# Light_Sensor_Card.net
KiCad netlist of a schematic drawn in EAGLE
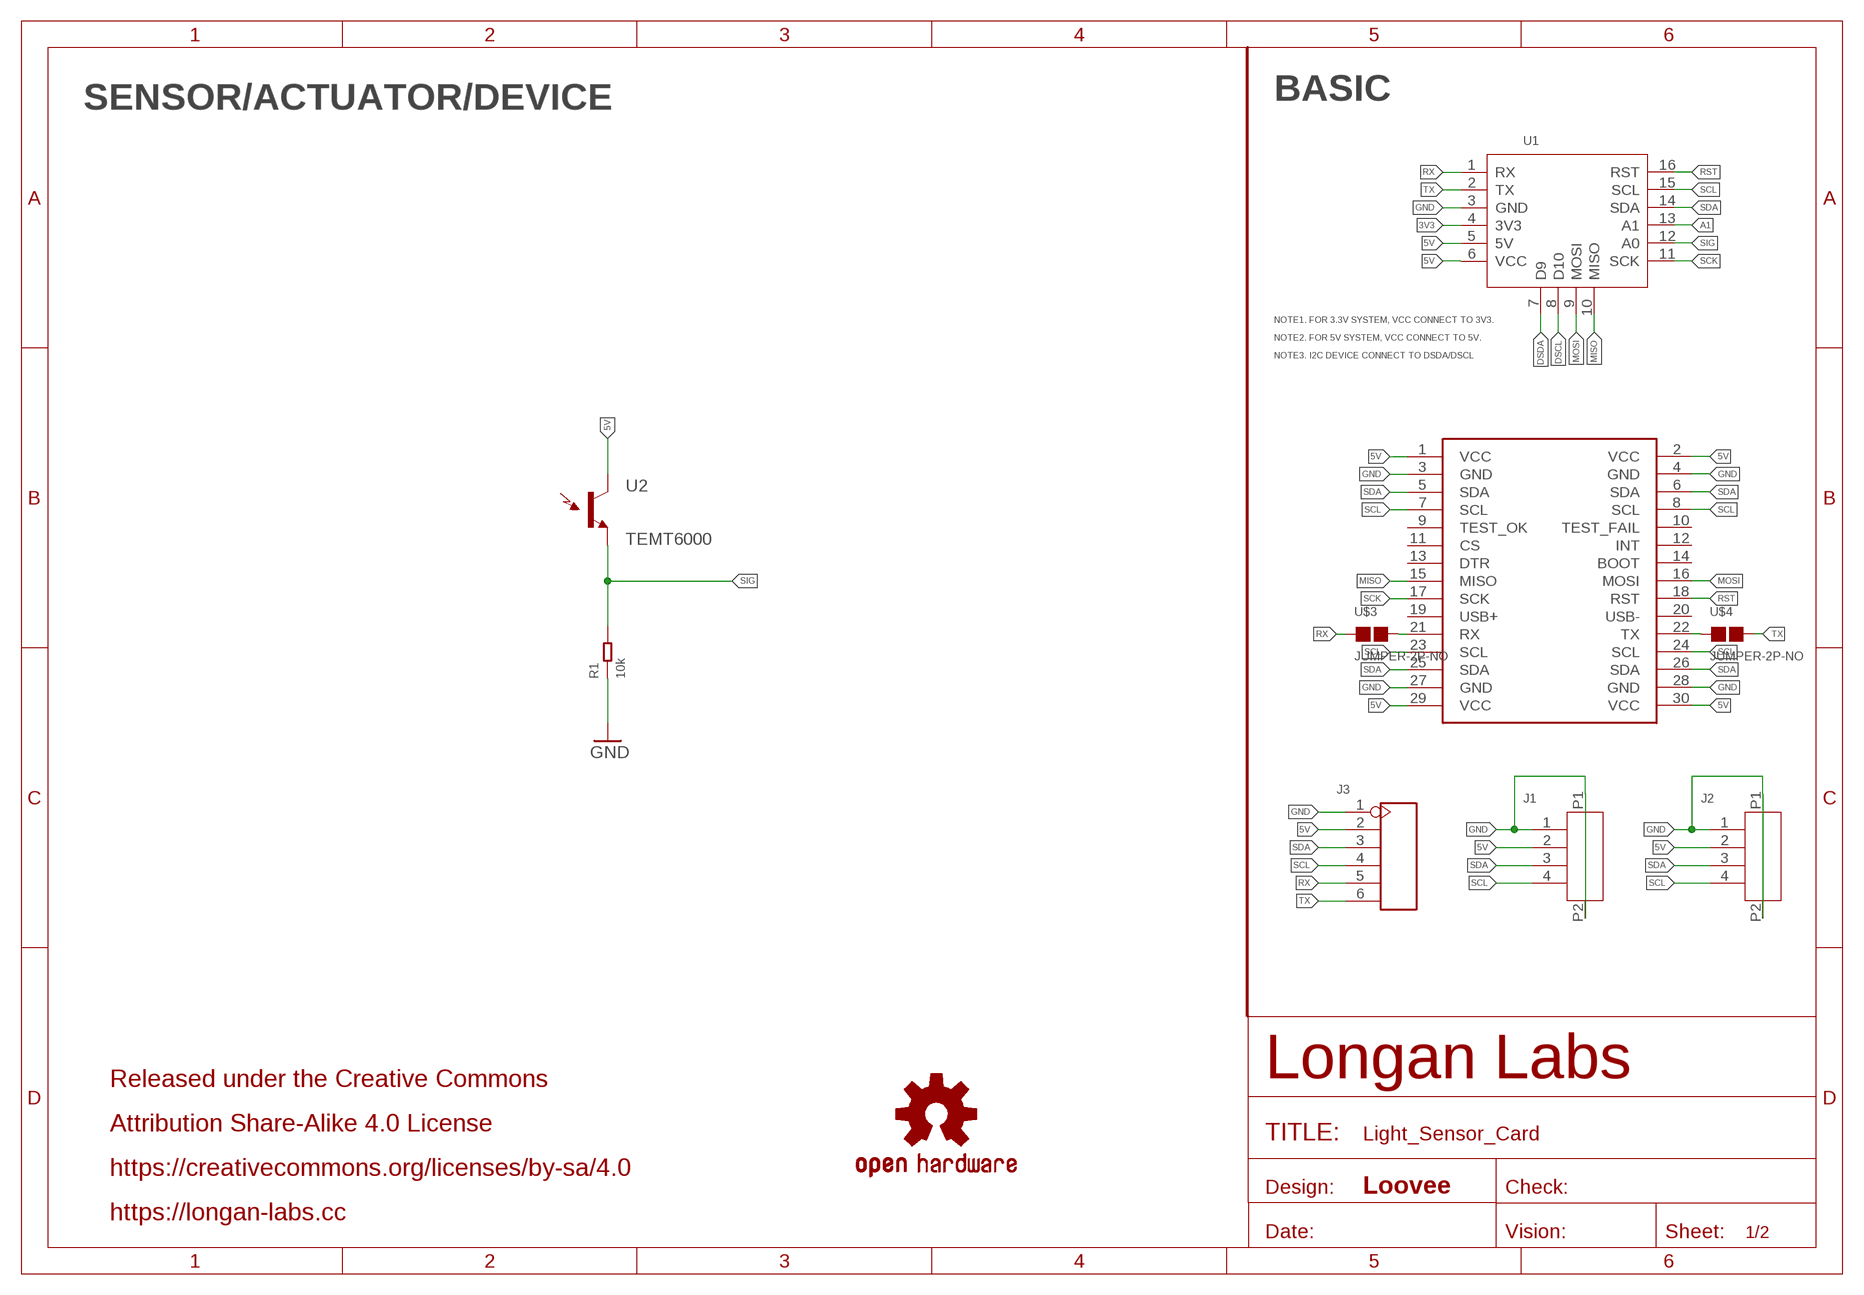
[diagram p0: schematic, sheet 1]

(export (version "E")
  (design (tool "Eeschema 10.0.6"))
  (components
    (comp (ref "J1")
      (value "HEADER-4P-1.0")
      (footprint "eagle-import:4P-1.0-90D")
      (libsource (lib "eagle-import") (part "HEADER-4P-1.0"))
    )
    (comp (ref "J2")
      (value "HEADER-4P-1.0")
      (footprint "eagle-import:4P-1.0-90D")
      (libsource (lib "eagle-import") (part "HEADER-4P-1.0"))
    )
    (comp (ref "J3")
      (value "HEADER-6P-55/35MIL")
      (footprint "eagle-import:H6-2.54")
      (libsource (lib "eagle-import") (part "HEADER-6P-55/35MIL"))
    )
    (comp (ref "LOGO2")
      (value "OSHW-LOGOS")
      (footprint "eagle-import:OSHW-LOGO-S")
      (libsource (lib "eagle-import") (part "OSHW-LOGOS"))
    )
    (comp (ref "MOUDLE1")
      (value "MOUDLE-2X15P-2.54'BOARD'")
      (footprint "eagle-import:MOUDLE-2X15P-2.54")
      (libsource (lib "eagle-import") (part "MOUDLE-2X15P-2.54'BOARD'"))
    )
    (comp (ref "R1")
      (value "10k")
      (footprint "eagle-import:R0603")
      (libsource (lib "eagle-import") (part "RES-0603"))
    )
    (comp (ref "U$3")
      (value "JUMPER-2P-NO")
      (footprint "eagle-import:2P-SMD-NO")
      (libsource (lib "eagle-import") (part "JUMPER-2P-NO"))
    )
    (comp (ref "U$4")
      (value "JUMPER-2P-NO")
      (footprint "eagle-import:2P-SMD-NO")
      (libsource (lib "eagle-import") (part "JUMPER-2P-NO"))
    )
    (comp (ref "U1")
      (value "MOUDLE-CARDS")
      (footprint "eagle-import:16P-2.0-CARDS")
      (libsource (lib "eagle-import") (part "MOUDLE-CARDS"))
    )
    (comp (ref "U2")
      (value "TEMT6000")
      (footprint "eagle-import:TEMT6000-SEN")
      (libsource (lib "eagle-import") (part "TEMT6000"))
    )
  )
  (nets
    (net (code "1") (name "3V3") (class "Default")
      (node (ref "U1") (pin "4") (pinfunction "3V3_4") (pintype "bidirectional"))
    )
    (net (code "2") (name "5V") (class "Default")
      (node (ref "J1") (pin "2") (pinfunction "2_2") (pintype "bidirectional"))
      (node (ref "J2") (pin "2") (pinfunction "2_2") (pintype "bidirectional"))
      (node (ref "J3") (pin "2") (pinfunction "2_2") (pintype "bidirectional"))
      (node (ref "MOUDLE1") (pin "1") (pinfunction "VCC_1") (pintype "bidirectional"))
      (node (ref "MOUDLE1") (pin "2") (pinfunction "VCC_2") (pintype "bidirectional"))
      (node (ref "MOUDLE1") (pin "29") (pinfunction "VCC_29") (pintype "bidirectional"))
      (node (ref "MOUDLE1") (pin "30") (pinfunction "VCC_30") (pintype "bidirectional"))
      (node (ref "U1") (pin "5") (pinfunction "5V_5") (pintype "bidirectional"))
      (node (ref "U1") (pin "6") (pinfunction "VCC_6") (pintype "bidirectional"))
      (node (ref "U2") (pin "COLLECTOR") (pinfunction "C1_COLLECTOR") (pintype "passive"))
    )
    (net (code "3") (name "A1") (class "Default")
      (node (ref "U1") (pin "13") (pinfunction "A1_13") (pintype "bidirectional"))
    )
    (net (code "4") (name "DSCL") (class "Default")
      (node (ref "U1") (pin "8") (pinfunction "D10_8") (pintype "bidirectional"))
    )
    (net (code "5") (name "DSDA") (class "Default")
      (node (ref "U1") (pin "7") (pinfunction "D9_7") (pintype "bidirectional"))
    )
    (net (code "6") (name "GND") (class "Default")
      (node (ref "J1") (pin "1") (pinfunction "1_1") (pintype "bidirectional"))
      (node (ref "J1") (pin "P1") (pinfunction "P1_P1") (pintype "bidirectional"))
      (node (ref "J1") (pin "P2") (pinfunction "P2_P2") (pintype "bidirectional"))
      (node (ref "J2") (pin "1") (pinfunction "1_1") (pintype "bidirectional"))
      (node (ref "J2") (pin "P1") (pinfunction "P1_P1") (pintype "bidirectional"))
      (node (ref "J2") (pin "P2") (pinfunction "P2_P2") (pintype "bidirectional"))
      (node (ref "J3") (pin "1") (pinfunction "1_1") (pintype "bidirectional"))
      (node (ref "MOUDLE1") (pin "27") (pinfunction "GND_27") (pintype "bidirectional"))
      (node (ref "MOUDLE1") (pin "28") (pinfunction "GND_28") (pintype "bidirectional"))
      (node (ref "MOUDLE1") (pin "3") (pinfunction "GND_3") (pintype "bidirectional"))
      (node (ref "MOUDLE1") (pin "4") (pinfunction "GND_4") (pintype "bidirectional"))
      (node (ref "R1") (pin "1") (pinfunction "1_1") (pintype "passive"))
      (node (ref "U1") (pin "3") (pinfunction "GND_3") (pintype "bidirectional"))
    )
    (net (code "7") (name "MISO") (class "Default")
      (node (ref "MOUDLE1") (pin "15") (pinfunction "MISO_15") (pintype "bidirectional"))
      (node (ref "U1") (pin "10") (pinfunction "MISO_10") (pintype "bidirectional"))
    )
    (net (code "8") (name "MOSI") (class "Default")
      (node (ref "MOUDLE1") (pin "16") (pinfunction "MOSI_16") (pintype "bidirectional"))
      (node (ref "U1") (pin "9") (pinfunction "MOSI_9") (pintype "bidirectional"))
    )
    (net (code "9") (name "Net-(MOUDLE1-RX)") (class "Default")
      (node (ref "MOUDLE1") (pin "21") (pinfunction "RX_21") (pintype "bidirectional"))
      (node (ref "U$3") (pin "2") (pinfunction "2_2") (pintype "bidirectional"))
    )
    (net (code "10") (name "Net-(MOUDLE1-TX)") (class "Default")
      (node (ref "MOUDLE1") (pin "22") (pinfunction "TX_22") (pintype "bidirectional"))
      (node (ref "U$4") (pin "1") (pinfunction "1_1") (pintype "bidirectional"))
    )
    (net (code "11") (name "RST") (class "Default")
      (node (ref "MOUDLE1") (pin "18") (pinfunction "RST_18") (pintype "bidirectional"))
      (node (ref "U1") (pin "16") (pinfunction "RST_16") (pintype "bidirectional"))
    )
    (net (code "12") (name "RX") (class "Default")
      (node (ref "J3") (pin "5") (pinfunction "5_5") (pintype "bidirectional"))
      (node (ref "U$3") (pin "1") (pinfunction "1_1") (pintype "bidirectional"))
      (node (ref "U1") (pin "1") (pinfunction "RX_1") (pintype "bidirectional"))
    )
    (net (code "13") (name "SCK") (class "Default")
      (node (ref "MOUDLE1") (pin "17") (pinfunction "SCK_17") (pintype "bidirectional"))
      (node (ref "U1") (pin "11") (pinfunction "SCK_11") (pintype "bidirectional"))
    )
    (net (code "14") (name "SCL") (class "Default")
      (node (ref "J1") (pin "4") (pinfunction "4_4") (pintype "bidirectional"))
      (node (ref "J2") (pin "4") (pinfunction "4_4") (pintype "bidirectional"))
      (node (ref "J3") (pin "4") (pinfunction "4_4") (pintype "bidirectional"))
      (node (ref "MOUDLE1") (pin "23") (pinfunction "SCL_23") (pintype "bidirectional"))
      (node (ref "MOUDLE1") (pin "24") (pinfunction "SCL_24") (pintype "bidirectional"))
      (node (ref "MOUDLE1") (pin "7") (pinfunction "SCL_7") (pintype "bidirectional"))
      (node (ref "MOUDLE1") (pin "8") (pinfunction "SCL_8") (pintype "bidirectional"))
      (node (ref "U1") (pin "15") (pinfunction "SCL_15") (pintype "bidirectional"))
    )
    (net (code "15") (name "SDA") (class "Default")
      (node (ref "J1") (pin "3") (pinfunction "3_3") (pintype "bidirectional"))
      (node (ref "J2") (pin "3") (pinfunction "3_3") (pintype "bidirectional"))
      (node (ref "J3") (pin "3") (pinfunction "3_3") (pintype "bidirectional"))
      (node (ref "MOUDLE1") (pin "25") (pinfunction "SDA_25") (pintype "bidirectional"))
      (node (ref "MOUDLE1") (pin "26") (pinfunction "SDA_26") (pintype "bidirectional"))
      (node (ref "MOUDLE1") (pin "5") (pinfunction "SDA_5") (pintype "bidirectional"))
      (node (ref "MOUDLE1") (pin "6") (pinfunction "SDA_6") (pintype "bidirectional"))
      (node (ref "U1") (pin "14") (pinfunction "SDA_14") (pintype "bidirectional"))
    )
    (net (code "16") (name "SIG") (class "Default")
      (node (ref "R1") (pin "2") (pinfunction "2_2") (pintype "passive"))
      (node (ref "U1") (pin "12") (pinfunction "A0_12") (pintype "bidirectional"))
      (node (ref "U2") (pin "EMITTER") (pinfunction "E1_EMITTER") (pintype "passive"))
    )
    (net (code "17") (name "TX") (class "Default")
      (node (ref "J3") (pin "6") (pinfunction "6_6") (pintype "bidirectional"))
      (node (ref "U$4") (pin "2") (pinfunction "2_2") (pintype "bidirectional"))
      (node (ref "U1") (pin "2") (pinfunction "TX_2") (pintype "bidirectional"))
    )
    (net (code "18") (name "unconnected-(MOUDLE1-BOOT-Pad14)") (class "Default")
      (node (ref "MOUDLE1") (pin "14") (pinfunction "BOOT_14") (pintype "bidirectional"))
    )
    (net (code "19") (name "unconnected-(MOUDLE1-CS-Pad11)") (class "Default")
      (node (ref "MOUDLE1") (pin "11") (pinfunction "CS_11") (pintype "bidirectional"))
    )
    (net (code "20") (name "unconnected-(MOUDLE1-DTR-Pad13)") (class "Default")
      (node (ref "MOUDLE1") (pin "13") (pinfunction "DTR_13") (pintype "bidirectional"))
    )
    (net (code "21") (name "unconnected-(MOUDLE1-INT-Pad12)") (class "Default")
      (node (ref "MOUDLE1") (pin "12") (pinfunction "INT_12") (pintype "bidirectional"))
    )
    (net (code "22") (name "unconnected-(MOUDLE1-TEST_FAIL-Pad10)") (class "Default")
      (node (ref "MOUDLE1") (pin "10") (pinfunction "TEST_FAIL_10") (pintype "bidirectional"))
    )
    (net (code "23") (name "unconnected-(MOUDLE1-TEST_OK-Pad9)") (class "Default")
      (node (ref "MOUDLE1") (pin "9") (pinfunction "TEST_OK_9") (pintype "bidirectional"))
    )
    (net (code "24") (name "unconnected-(MOUDLE1-USB+-Pad19)") (class "Default")
      (node (ref "MOUDLE1") (pin "19") (pinfunction "USB+_19") (pintype "bidirectional"))
    )
    (net (code "25") (name "unconnected-(MOUDLE1-USB--Pad20)") (class "Default")
      (node (ref "MOUDLE1") (pin "20") (pinfunction "USB-_20") (pintype "bidirectional"))
    )
  )
)
